# RPI_3.net
KiCad netlist of a schematic drawn in Altium Designer
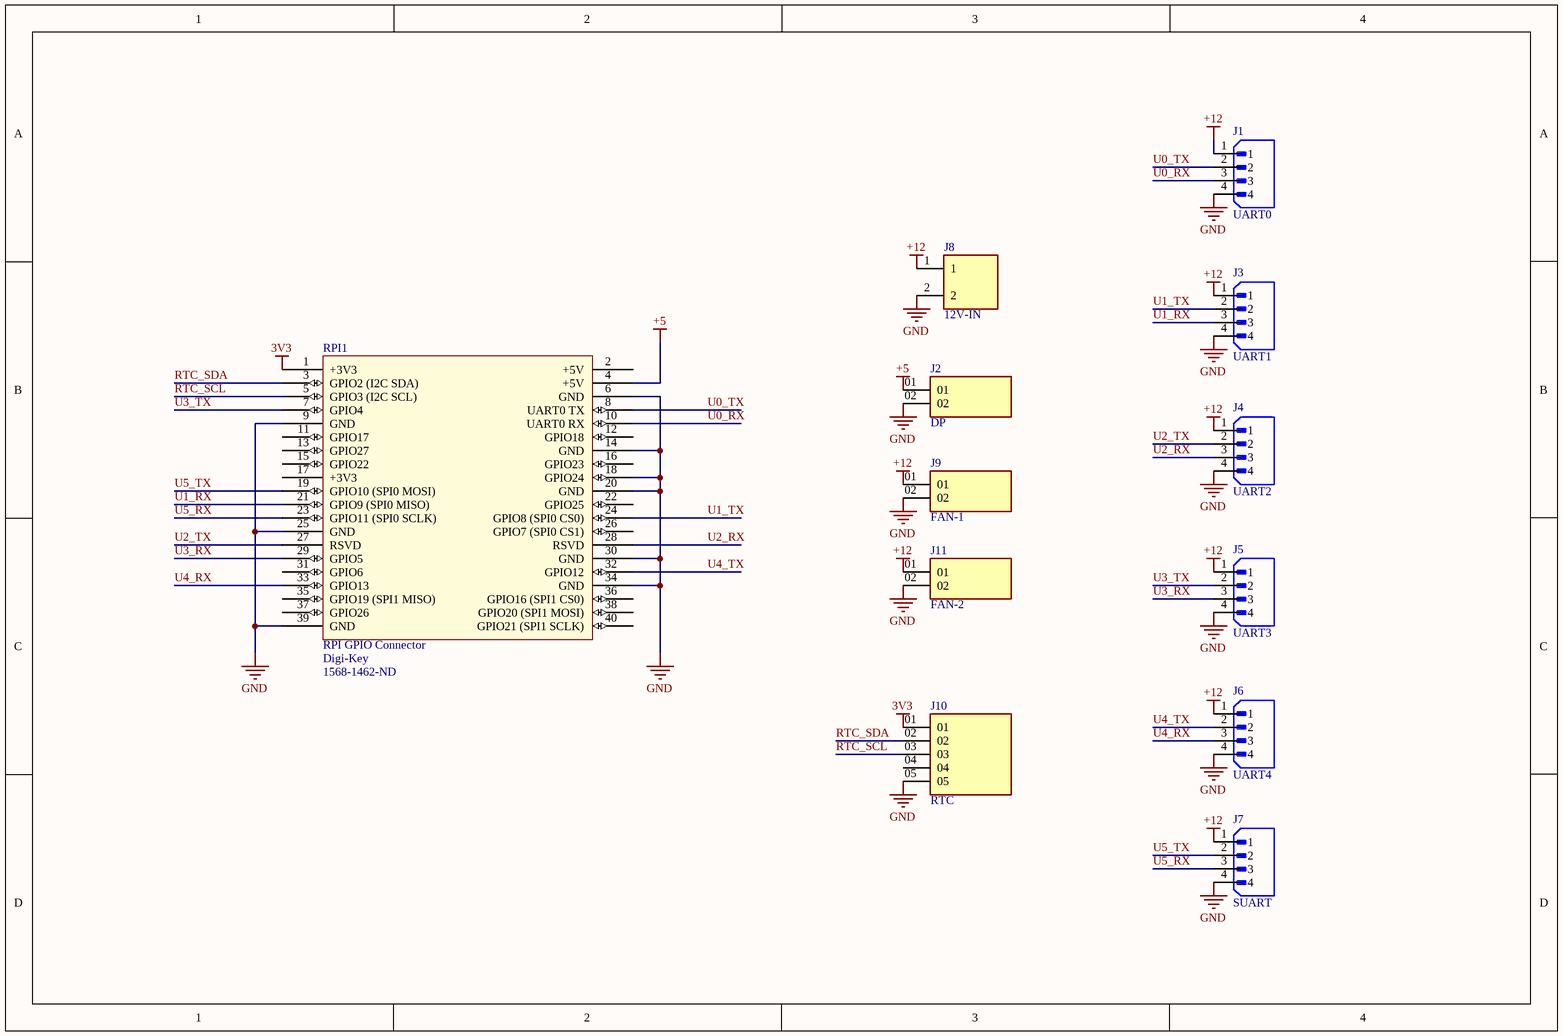
[diagram p0: RPI 3.SchDoc]

(export (version "E")
  (design (tool "Eeschema 10.0.6"))
  (components
    (comp (ref "J1")
      (value "UART0")
      (footprint "JST_B4B-XH-A(LF)(SN)")
      (description "Connector Header Through Hole 4 position 0.098 (2.50mm)")
      (fields (field (name "MF") "JST Sales") (field (name "MP") "B4B-XH-A(LF)(SN)"))
      (libsource (lib "B4B-XH-A_LF__SN_") (part "B4B-XH-A(LF)(SN)"))
    )
    (comp (ref "J2")
      (value "DP")
      (footprint "SAMTEC_TSW-102-24-L-S")
      (description "Connector Header Through Hole 2 position 0.100 (2.54mm)")
      (fields (field (name "MP") "TSW-102-24-L-S") (field (name "MF") "Samtec"))
      (libsource (lib "TSW-102-24-L-S") (part "TSW-102-24-L-S"))
    )
    (comp (ref "J3")
      (value "UART1")
      (footprint "JST_B4B-XH-A(LF)(SN)")
      (description "Connector Header Through Hole 4 position 0.098 (2.50mm)")
      (fields (field (name "MF") "JST Sales") (field (name "MP") "B4B-XH-A(LF)(SN)"))
      (libsource (lib "B4B-XH-A_LF__SN_") (part "B4B-XH-A(LF)(SN)"))
    )
    (comp (ref "J4")
      (value "UART2")
      (footprint "JST_B4B-XH-A(LF)(SN)")
      (description "Connector Header Through Hole 4 position 0.098 (2.50mm)")
      (fields (field (name "MF") "JST Sales") (field (name "MP") "B4B-XH-A(LF)(SN)"))
      (libsource (lib "B4B-XH-A_LF__SN_") (part "B4B-XH-A(LF)(SN)"))
    )
    (comp (ref "J5")
      (value "UART3")
      (footprint "JST_B4B-XH-A(LF)(SN)")
      (description "Connector Header Through Hole 4 position 0.098 (2.50mm)")
      (fields (field (name "MF") "JST Sales") (field (name "MP") "B4B-XH-A(LF)(SN)"))
      (libsource (lib "B4B-XH-A_LF__SN_") (part "B4B-XH-A(LF)(SN)"))
    )
    (comp (ref "J6")
      (value "UART4")
      (footprint "JST_B4B-XH-A(LF)(SN)")
      (description "Connector Header Through Hole 4 position 0.098 (2.50mm)")
      (fields (field (name "MF") "JST Sales") (field (name "MP") "B4B-XH-A(LF)(SN)"))
      (libsource (lib "B4B-XH-A_LF__SN_") (part "B4B-XH-A(LF)(SN)"))
    )
    (comp (ref "J7")
      (value "SUART")
      (footprint "JST_B4B-XH-A(LF)(SN)")
      (description "Connector Header Through Hole 4 position 0.098 (2.50mm)")
      (fields (field (name "MF") "JST Sales") (field (name "MP") "B4B-XH-A(LF)(SN)"))
      (libsource (lib "B4B-XH-A_LF__SN_") (part "B4B-XH-A(LF)(SN)"))
    )
    (comp (ref "J8")
      (value "12V-IN")
      (footprint "HANDSON_KF301-2P")
      (description "2 Pin Terminal Block 5mm Pitch")
      (fields (field (name "MP") "KF301-2P"))
      (libsource (lib "KF301-2P") (part "KF301-2P"))
    )
    (comp (ref "J9")
      (value "FAN-1")
      (footprint "SAMTEC_TSW-102-24-L-S")
      (description "Connector Header Through Hole 2 position 0.100 (2.54mm)")
      (fields (field (name "MP") "TSW-102-24-L-S") (field (name "MF") "Samtec"))
      (libsource (lib "TSW-102-24-L-S") (part "TSW-102-24-L-S"))
    )
    (comp (ref "J10")
      (value "RTC")
      (footprint "SAMTEC_TLW-105-06-T-S")
      (fields (field (name "MP") "TLW-105-06-T-S"))
      (libsource (lib "TLW-105-06-T-S") (part "TLW-105-06-T-S"))
    )
    (comp (ref "J11")
      (value "FAN-2")
      (footprint "SAMTEC_TSW-102-24-L-S")
      (description "Connector Header Through Hole 2 position 0.100 (2.54mm)")
      (fields (field (name "MP") "TSW-102-24-L-S") (field (name "MF") "Samtec"))
      (libsource (lib "TSW-102-24-L-S") (part "TSW-102-24-L-S"))
    )
    (comp (ref "RPI1")
      (value "RPI GPIO Connector")
      (footprint "rpi")
      (description "GPIO Header for Raspberry Pi A+/B+/Pi 2/Pi 3 - 2x20")
      (fields
        (field (name "MANUFACTURER") "SparkFun Electronics")
        (field (name "MANUFACTURER PART NUMBER") "PRT-14017")
        (field (name "SUPPLIER 1") "Digi-Key")
        (field (name "SUPPLIER PART NUMBER 1") "1568-1462-ND")
      )
      (libsource (lib "rpi") (part "rpi connector"))
    )
  )
  (nets
    (net (code "1") (name "+5") (class "Default")
      (node (ref "J2") (pin "01") (pinfunction "01_01") (pintype "passive"))
      (node (ref "RPI1") (pin "4") (pinfunction "+5V_4") (pintype "power_in"))
    )
    (net (code "2") (name "+12") (class "Default")
      (node (ref "J1") (pin "1") (pinfunction "1_1") (pintype "passive"))
      (node (ref "J11") (pin "01") (pinfunction "01_01") (pintype "passive"))
      (node (ref "J3") (pin "1") (pinfunction "1_1") (pintype "passive"))
      (node (ref "J4") (pin "1") (pinfunction "1_1") (pintype "passive"))
      (node (ref "J5") (pin "1") (pinfunction "1_1") (pintype "passive"))
      (node (ref "J6") (pin "1") (pinfunction "1_1") (pintype "passive"))
      (node (ref "J7") (pin "1") (pinfunction "1_1") (pintype "passive"))
      (node (ref "J8") (pin "1") (pinfunction "1_1") (pintype "passive"))
      (node (ref "J9") (pin "01") (pinfunction "01_01") (pintype "passive"))
    )
    (net (code "3") (name "/RTC_SCL") (class "Default")
      (node (ref "J10") (pin "03") (pinfunction "03_03") (pintype "passive"))
      (node (ref "RPI1") (pin "5") (pinfunction "GPIO3_(I2C_SCL)_5") (pintype "bidirectional"))
    )
    (net (code "4") (name "/RTC_SDA") (class "Default")
      (node (ref "J10") (pin "02") (pinfunction "02_02") (pintype "passive"))
      (node (ref "RPI1") (pin "3") (pinfunction "GPIO2_(I2C_SDA)_3") (pintype "bidirectional"))
    )
    (net (code "5") (name "/U0_RX") (class "Default")
      (node (ref "J1") (pin "3") (pinfunction "3_3") (pintype "passive"))
      (node (ref "RPI1") (pin "10") (pinfunction "UART0_RX_10") (pintype "bidirectional"))
    )
    (net (code "6") (name "/U0_TX") (class "Default")
      (node (ref "J1") (pin "2") (pinfunction "2_2") (pintype "passive"))
      (node (ref "RPI1") (pin "8") (pinfunction "UART0_TX_8") (pintype "bidirectional"))
    )
    (net (code "7") (name "/U1_RX") (class "Default")
      (node (ref "J3") (pin "3") (pinfunction "3_3") (pintype "passive"))
      (node (ref "RPI1") (pin "21") (pinfunction "GPIO9_(SPI0_MISO)_21") (pintype "bidirectional"))
    )
    (net (code "8") (name "/U1_TX") (class "Default")
      (node (ref "J3") (pin "2") (pinfunction "2_2") (pintype "passive"))
      (node (ref "RPI1") (pin "24") (pinfunction "GPIO8_(SPI0_CS0)_24") (pintype "bidirectional"))
    )
    (net (code "9") (name "/U2_RX") (class "Default")
      (node (ref "J4") (pin "3") (pinfunction "3_3") (pintype "passive"))
      (node (ref "RPI1") (pin "28") (pinfunction "RSVD_28") (pintype "passive"))
    )
    (net (code "10") (name "/U2_TX") (class "Default")
      (node (ref "J4") (pin "2") (pinfunction "2_2") (pintype "passive"))
      (node (ref "RPI1") (pin "27") (pinfunction "RSVD_27") (pintype "passive"))
    )
    (net (code "11") (name "/U3_RX") (class "Default")
      (node (ref "J5") (pin "3") (pinfunction "3_3") (pintype "passive"))
      (node (ref "RPI1") (pin "29") (pinfunction "GPIO5_29") (pintype "bidirectional"))
    )
    (net (code "12") (name "/U3_TX") (class "Default")
      (node (ref "J5") (pin "2") (pinfunction "2_2") (pintype "passive"))
      (node (ref "RPI1") (pin "7") (pinfunction "GPIO4_7") (pintype "bidirectional"))
    )
    (net (code "13") (name "/U4_RX") (class "Default")
      (node (ref "J6") (pin "3") (pinfunction "3_3") (pintype "passive"))
      (node (ref "RPI1") (pin "33") (pinfunction "GPIO13_33") (pintype "bidirectional"))
    )
    (net (code "14") (name "/U4_TX") (class "Default")
      (node (ref "J6") (pin "2") (pinfunction "2_2") (pintype "passive"))
      (node (ref "RPI1") (pin "32") (pinfunction "GPIO12_32") (pintype "bidirectional"))
    )
    (net (code "15") (name "/U5_RX") (class "Default")
      (node (ref "J7") (pin "3") (pinfunction "3_3") (pintype "passive"))
      (node (ref "RPI1") (pin "23") (pinfunction "GPIO11_(SPI0_SCLK)_23") (pintype "bidirectional"))
    )
    (net (code "16") (name "/U5_TX") (class "Default")
      (node (ref "J7") (pin "2") (pinfunction "2_2") (pintype "passive"))
      (node (ref "RPI1") (pin "19") (pinfunction "GPIO10_(SPI0_MOSI)_19") (pintype "bidirectional"))
    )
    (net (code "17") (name "3V3") (class "Default")
      (node (ref "J10") (pin "01") (pinfunction "01_01") (pintype "passive"))
      (node (ref "RPI1") (pin "1") (pinfunction "+3V3_1") (pintype "power_in"))
    )
    (net (code "18") (name "GND") (class "Default")
      (node (ref "J1") (pin "4") (pinfunction "4_4") (pintype "passive"))
      (node (ref "J10") (pin "05") (pinfunction "05_05") (pintype "passive"))
      (node (ref "J11") (pin "02") (pinfunction "02_02") (pintype "passive"))
      (node (ref "J2") (pin "02") (pinfunction "02_02") (pintype "passive"))
      (node (ref "J3") (pin "4") (pinfunction "4_4") (pintype "passive"))
      (node (ref "J4") (pin "4") (pinfunction "4_4") (pintype "passive"))
      (node (ref "J5") (pin "4") (pinfunction "4_4") (pintype "passive"))
      (node (ref "J6") (pin "4") (pinfunction "4_4") (pintype "passive"))
      (node (ref "J7") (pin "4") (pinfunction "4_4") (pintype "passive"))
      (node (ref "J8") (pin "2") (pinfunction "2_2") (pintype "passive"))
      (node (ref "J9") (pin "02") (pinfunction "02_02") (pintype "passive"))
      (node (ref "RPI1") (pin "14") (pinfunction "GND_14") (pintype "power_in"))
      (node (ref "RPI1") (pin "18") (pinfunction "GPIO24_18") (pintype "bidirectional"))
      (node (ref "RPI1") (pin "20") (pinfunction "GND_20") (pintype "power_in"))
      (node (ref "RPI1") (pin "25") (pinfunction "GND_25") (pintype "power_in"))
      (node (ref "RPI1") (pin "30") (pinfunction "GND_30") (pintype "power_in"))
      (node (ref "RPI1") (pin "34") (pinfunction "GND_34") (pintype "passive"))
      (node (ref "RPI1") (pin "39") (pinfunction "GND_39") (pintype "power_in"))
      (node (ref "RPI1") (pin "6") (pinfunction "GND_6") (pintype "power_in"))
      (node (ref "RPI1") (pin "9") (pinfunction "GND_9") (pintype "power_in"))
    )
    (net (code "19") (name "unconnected-(J10-Pad04)") (class "Default")
      (node (ref "J10") (pin "04") (pinfunction "04_04") (pintype "passive"))
    )
    (net (code "20") (name "unconnected-(RPI1-+3V3-Pad17)") (class "Default")
      (node (ref "RPI1") (pin "17") (pinfunction "+3V3_17") (pintype "power_in"))
    )
    (net (code "21") (name "unconnected-(RPI1-+5V-Pad2)") (class "Default")
      (node (ref "RPI1") (pin "2") (pinfunction "+5V_2") (pintype "power_in"))
    )
    (net (code "22") (name "unconnected-(RPI1-GPIO6-Pad31)") (class "Default")
      (node (ref "RPI1") (pin "31") (pinfunction "GPIO6_31") (pintype "bidirectional"))
    )
    (net (code "23") (name "unconnected-(RPI1-GPIO7_(SPI0_CS1)-Pad26)") (class "Default")
      (node (ref "RPI1") (pin "26") (pinfunction "GPIO7_(SPI0_CS1)_26") (pintype "bidirectional"))
    )
    (net (code "24") (name "unconnected-(RPI1-GPIO16_(SPI1_CS0)-Pad36)") (class "Default")
      (node (ref "RPI1") (pin "36") (pinfunction "GPIO16_(SPI1_CS0)_36") (pintype "bidirectional"))
    )
    (net (code "25") (name "unconnected-(RPI1-GPIO17-Pad11)") (class "Default")
      (node (ref "RPI1") (pin "11") (pinfunction "GPIO17_11") (pintype "bidirectional"))
    )
    (net (code "26") (name "unconnected-(RPI1-GPIO18-Pad12)") (class "Default")
      (node (ref "RPI1") (pin "12") (pinfunction "GPIO18_12") (pintype "bidirectional"))
    )
    (net (code "27") (name "unconnected-(RPI1-GPIO19_(SPI1_MISO)-Pad35)") (class "Default")
      (node (ref "RPI1") (pin "35") (pinfunction "GPIO19_(SPI1_MISO)_35") (pintype "bidirectional"))
    )
    (net (code "28") (name "unconnected-(RPI1-GPIO20_(SPI1_MOSI)-Pad38)") (class "Default")
      (node (ref "RPI1") (pin "38") (pinfunction "GPIO20_(SPI1_MOSI)_38") (pintype "bidirectional"))
    )
    (net (code "29") (name "unconnected-(RPI1-GPIO21_(SPI1_SCLK)-Pad40)") (class "Default")
      (node (ref "RPI1") (pin "40") (pinfunction "GPIO21_(SPI1_SCLK)_40") (pintype "bidirectional"))
    )
    (net (code "30") (name "unconnected-(RPI1-GPIO22-Pad15)") (class "Default")
      (node (ref "RPI1") (pin "15") (pinfunction "GPIO22_15") (pintype "bidirectional"))
    )
    (net (code "31") (name "unconnected-(RPI1-GPIO23-Pad16)") (class "Default")
      (node (ref "RPI1") (pin "16") (pinfunction "GPIO23_16") (pintype "bidirectional"))
    )
    (net (code "32") (name "unconnected-(RPI1-GPIO25-Pad22)") (class "Default")
      (node (ref "RPI1") (pin "22") (pinfunction "GPIO25_22") (pintype "bidirectional"))
    )
    (net (code "33") (name "unconnected-(RPI1-GPIO26-Pad37)") (class "Default")
      (node (ref "RPI1") (pin "37") (pinfunction "GPIO26_37") (pintype "bidirectional"))
    )
    (net (code "34") (name "unconnected-(RPI1-GPIO27-Pad13)") (class "Default")
      (node (ref "RPI1") (pin "13") (pinfunction "GPIO27_13") (pintype "bidirectional"))
    )
  )
)
